# 44-pin_QFN_TQFP.net
KiCad netlist of a schematic drawn in EAGLE
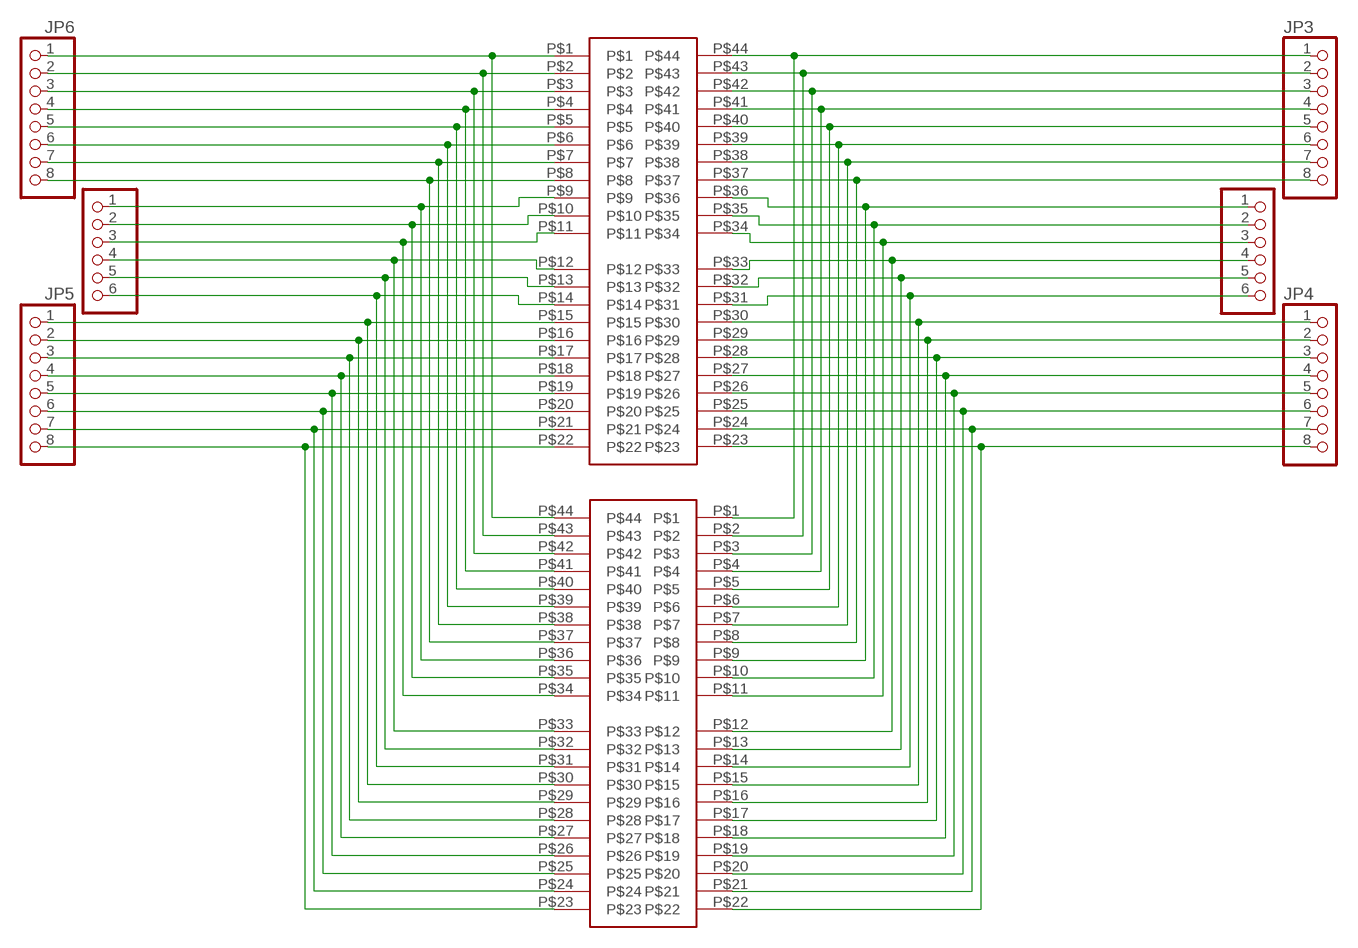
[diagram p0: schematic, sheet 1]

(export (version "E")
  (design (tool "Eeschema 10.0.6"))
  (components
    (comp (ref "JP1")
      (value "PADS-6")
      (footprint "eagle-import:PADS-6")
      (libsource (lib "eagle-import") (part "PADS-6"))
    )
    (comp (ref "JP2")
      (value "PADS-6")
      (footprint "eagle-import:PADS-6")
      (libsource (lib "eagle-import") (part "PADS-6"))
    )
    (comp (ref "JP3")
      (value "PADS-8CLEANBIG")
      (footprint "eagle-import:PADS-8")
      (libsource (lib "eagle-import") (part "PADS-8CLEANBIG"))
    )
    (comp (ref "JP4")
      (value "PADS-8CLEANBIG")
      (footprint "eagle-import:PADS-8")
      (libsource (lib "eagle-import") (part "PADS-8CLEANBIG"))
    )
    (comp (ref "JP5")
      (value "PADS-8CLEANBIG")
      (footprint "eagle-import:PADS-8")
      (libsource (lib "eagle-import") (part "PADS-8CLEANBIG"))
    )
    (comp (ref "JP6")
      (value "PADS-8CLEANBIG")
      (footprint "eagle-import:PADS-8")
      (libsource (lib "eagle-import") (part "PADS-8CLEANBIG"))
    )
    (comp (ref "U$1")
      (value "44-PINQFN")
      (footprint "eagle-import:QFN44")
      (libsource (lib "eagle-import") (part "44-PINQFN"))
    )
    (comp (ref "U$2")
      (value "44-PINTQFP")
      (footprint "eagle-import:TQFP44")
      (libsource (lib "eagle-import") (part "44-PINTQFP"))
    )
  )
  (nets
    (net (code "1") (name "Net-(JP1-Pad1)") (class "Default")
      (node (ref "JP1") (pin "1") (pinfunction "1_1") (pintype "passive"))
      (node (ref "U$1") (pin "P$36") (pinfunction "P$36_P$36") (pintype "bidirectional"))
      (node (ref "U$2") (pin "P$9") (pinfunction "P$9_P$9") (pintype "bidirectional"))
    )
    (net (code "2") (name "Net-(JP1-Pad2)") (class "Default")
      (node (ref "JP1") (pin "2") (pinfunction "2_2") (pintype "passive"))
      (node (ref "U$1") (pin "P$35") (pinfunction "P$35_P$35") (pintype "bidirectional"))
      (node (ref "U$2") (pin "P$10") (pinfunction "P$10_P$10") (pintype "bidirectional"))
    )
    (net (code "3") (name "Net-(JP1-Pad3)") (class "Default")
      (node (ref "JP1") (pin "3") (pinfunction "3_3") (pintype "passive"))
      (node (ref "U$1") (pin "P$34") (pinfunction "P$34_P$34") (pintype "bidirectional"))
      (node (ref "U$2") (pin "P$11") (pinfunction "P$11_P$11") (pintype "bidirectional"))
    )
    (net (code "4") (name "Net-(JP1-Pad4)") (class "Default")
      (node (ref "JP1") (pin "4") (pinfunction "4_4") (pintype "passive"))
      (node (ref "U$1") (pin "P$33") (pinfunction "P$33_P$33") (pintype "bidirectional"))
      (node (ref "U$2") (pin "P$12") (pinfunction "P$12_P$12") (pintype "bidirectional"))
    )
    (net (code "5") (name "Net-(JP1-Pad5)") (class "Default")
      (node (ref "JP1") (pin "5") (pinfunction "5_5") (pintype "passive"))
      (node (ref "U$1") (pin "P$32") (pinfunction "P$32_P$32") (pintype "bidirectional"))
      (node (ref "U$2") (pin "P$13") (pinfunction "P$13_P$13") (pintype "bidirectional"))
    )
    (net (code "6") (name "Net-(JP1-Pad6)") (class "Default")
      (node (ref "JP1") (pin "6") (pinfunction "6_6") (pintype "passive"))
      (node (ref "U$1") (pin "P$31") (pinfunction "P$31_P$31") (pintype "bidirectional"))
      (node (ref "U$2") (pin "P$14") (pinfunction "P$14_P$14") (pintype "bidirectional"))
    )
    (net (code "7") (name "Net-(JP2-Pad1)") (class "Default")
      (node (ref "JP2") (pin "1") (pinfunction "1_1") (pintype "passive"))
      (node (ref "U$1") (pin "P$9") (pinfunction "P$9_P$9") (pintype "bidirectional"))
      (node (ref "U$2") (pin "P$36") (pinfunction "P$36_P$36") (pintype "bidirectional"))
    )
    (net (code "8") (name "Net-(JP2-Pad2)") (class "Default")
      (node (ref "JP2") (pin "2") (pinfunction "2_2") (pintype "passive"))
      (node (ref "U$1") (pin "P$10") (pinfunction "P$10_P$10") (pintype "bidirectional"))
      (node (ref "U$2") (pin "P$35") (pinfunction "P$35_P$35") (pintype "bidirectional"))
    )
    (net (code "9") (name "Net-(JP2-Pad3)") (class "Default")
      (node (ref "JP2") (pin "3") (pinfunction "3_3") (pintype "passive"))
      (node (ref "U$1") (pin "P$11") (pinfunction "P$11_P$11") (pintype "bidirectional"))
      (node (ref "U$2") (pin "P$34") (pinfunction "P$34_P$34") (pintype "bidirectional"))
    )
    (net (code "10") (name "Net-(JP2-Pad4)") (class "Default")
      (node (ref "JP2") (pin "4") (pinfunction "4_4") (pintype "passive"))
      (node (ref "U$1") (pin "P$12") (pinfunction "P$12_P$12") (pintype "bidirectional"))
      (node (ref "U$2") (pin "P$33") (pinfunction "P$33_P$33") (pintype "bidirectional"))
    )
    (net (code "11") (name "Net-(JP2-Pad5)") (class "Default")
      (node (ref "JP2") (pin "5") (pinfunction "5_5") (pintype "passive"))
      (node (ref "U$1") (pin "P$13") (pinfunction "P$13_P$13") (pintype "bidirectional"))
      (node (ref "U$2") (pin "P$32") (pinfunction "P$32_P$32") (pintype "bidirectional"))
    )
    (net (code "12") (name "Net-(JP2-Pad6)") (class "Default")
      (node (ref "JP2") (pin "6") (pinfunction "6_6") (pintype "passive"))
      (node (ref "U$1") (pin "P$14") (pinfunction "P$14_P$14") (pintype "bidirectional"))
      (node (ref "U$2") (pin "P$31") (pinfunction "P$31_P$31") (pintype "bidirectional"))
    )
    (net (code "13") (name "Net-(JP3-Pad1)") (class "Default")
      (node (ref "JP3") (pin "1") (pinfunction "1_1") (pintype "passive"))
      (node (ref "U$1") (pin "P$44") (pinfunction "P$44_P$44") (pintype "bidirectional"))
      (node (ref "U$2") (pin "P$1") (pinfunction "P$1_P$1") (pintype "bidirectional"))
    )
    (net (code "14") (name "Net-(JP3-Pad2)") (class "Default")
      (node (ref "JP3") (pin "2") (pinfunction "2_2") (pintype "passive"))
      (node (ref "U$1") (pin "P$43") (pinfunction "P$43_P$43") (pintype "bidirectional"))
      (node (ref "U$2") (pin "P$2") (pinfunction "P$2_P$2") (pintype "bidirectional"))
    )
    (net (code "15") (name "Net-(JP3-Pad3)") (class "Default")
      (node (ref "JP3") (pin "3") (pinfunction "3_3") (pintype "passive"))
      (node (ref "U$1") (pin "P$42") (pinfunction "P$42_P$42") (pintype "bidirectional"))
      (node (ref "U$2") (pin "P$3") (pinfunction "P$3_P$3") (pintype "bidirectional"))
    )
    (net (code "16") (name "Net-(JP3-Pad4)") (class "Default")
      (node (ref "JP3") (pin "4") (pinfunction "4_4") (pintype "passive"))
      (node (ref "U$1") (pin "P$41") (pinfunction "P$41_P$41") (pintype "bidirectional"))
      (node (ref "U$2") (pin "P$4") (pinfunction "P$4_P$4") (pintype "bidirectional"))
    )
    (net (code "17") (name "Net-(JP3-Pad5)") (class "Default")
      (node (ref "JP3") (pin "5") (pinfunction "5_5") (pintype "passive"))
      (node (ref "U$1") (pin "P$40") (pinfunction "P$40_P$40") (pintype "bidirectional"))
      (node (ref "U$2") (pin "P$5") (pinfunction "P$5_P$5") (pintype "bidirectional"))
    )
    (net (code "18") (name "Net-(JP3-Pad6)") (class "Default")
      (node (ref "JP3") (pin "6") (pinfunction "6_6") (pintype "passive"))
      (node (ref "U$1") (pin "P$39") (pinfunction "P$39_P$39") (pintype "bidirectional"))
      (node (ref "U$2") (pin "P$6") (pinfunction "P$6_P$6") (pintype "bidirectional"))
    )
    (net (code "19") (name "Net-(JP3-Pad7)") (class "Default")
      (node (ref "JP3") (pin "7") (pinfunction "7_7") (pintype "passive"))
      (node (ref "U$1") (pin "P$38") (pinfunction "P$38_P$38") (pintype "bidirectional"))
      (node (ref "U$2") (pin "P$7") (pinfunction "P$7_P$7") (pintype "bidirectional"))
    )
    (net (code "20") (name "Net-(JP3-Pad8)") (class "Default")
      (node (ref "JP3") (pin "8") (pinfunction "8_8") (pintype "passive"))
      (node (ref "U$1") (pin "P$37") (pinfunction "P$37_P$37") (pintype "bidirectional"))
      (node (ref "U$2") (pin "P$8") (pinfunction "P$8_P$8") (pintype "bidirectional"))
    )
    (net (code "21") (name "Net-(JP4-Pad1)") (class "Default")
      (node (ref "JP4") (pin "1") (pinfunction "1_1") (pintype "passive"))
      (node (ref "U$1") (pin "P$30") (pinfunction "P$30_P$30") (pintype "bidirectional"))
      (node (ref "U$2") (pin "P$15") (pinfunction "P$15_P$15") (pintype "bidirectional"))
    )
    (net (code "22") (name "Net-(JP4-Pad2)") (class "Default")
      (node (ref "JP4") (pin "2") (pinfunction "2_2") (pintype "passive"))
      (node (ref "U$1") (pin "P$29") (pinfunction "P$29_P$29") (pintype "bidirectional"))
      (node (ref "U$2") (pin "P$16") (pinfunction "P$16_P$16") (pintype "bidirectional"))
    )
    (net (code "23") (name "Net-(JP4-Pad3)") (class "Default")
      (node (ref "JP4") (pin "3") (pinfunction "3_3") (pintype "passive"))
      (node (ref "U$1") (pin "P$28") (pinfunction "P$28_P$28") (pintype "bidirectional"))
      (node (ref "U$2") (pin "P$17") (pinfunction "P$17_P$17") (pintype "bidirectional"))
    )
    (net (code "24") (name "Net-(JP4-Pad4)") (class "Default")
      (node (ref "JP4") (pin "4") (pinfunction "4_4") (pintype "passive"))
      (node (ref "U$1") (pin "P$27") (pinfunction "P$27_P$27") (pintype "bidirectional"))
      (node (ref "U$2") (pin "P$18") (pinfunction "P$18_P$18") (pintype "bidirectional"))
    )
    (net (code "25") (name "Net-(JP4-Pad5)") (class "Default")
      (node (ref "JP4") (pin "5") (pinfunction "5_5") (pintype "passive"))
      (node (ref "U$1") (pin "P$26") (pinfunction "P$26_P$26") (pintype "bidirectional"))
      (node (ref "U$2") (pin "P$19") (pinfunction "P$19_P$19") (pintype "bidirectional"))
    )
    (net (code "26") (name "Net-(JP4-Pad6)") (class "Default")
      (node (ref "JP4") (pin "6") (pinfunction "6_6") (pintype "passive"))
      (node (ref "U$1") (pin "P$25") (pinfunction "P$25_P$25") (pintype "bidirectional"))
      (node (ref "U$2") (pin "P$20") (pinfunction "P$20_P$20") (pintype "bidirectional"))
    )
    (net (code "27") (name "Net-(JP4-Pad7)") (class "Default")
      (node (ref "JP4") (pin "7") (pinfunction "7_7") (pintype "passive"))
      (node (ref "U$1") (pin "P$24") (pinfunction "P$24_P$24") (pintype "bidirectional"))
      (node (ref "U$2") (pin "P$21") (pinfunction "P$21_P$21") (pintype "bidirectional"))
    )
    (net (code "28") (name "Net-(JP4-Pad8)") (class "Default")
      (node (ref "JP4") (pin "8") (pinfunction "8_8") (pintype "passive"))
      (node (ref "U$1") (pin "P$23") (pinfunction "P$23_P$23") (pintype "bidirectional"))
      (node (ref "U$2") (pin "P$22") (pinfunction "P$22_P$22") (pintype "bidirectional"))
    )
    (net (code "29") (name "Net-(JP5-Pad1)") (class "Default")
      (node (ref "JP5") (pin "1") (pinfunction "1_1") (pintype "passive"))
      (node (ref "U$1") (pin "P$15") (pinfunction "P$15_P$15") (pintype "bidirectional"))
      (node (ref "U$2") (pin "P$30") (pinfunction "P$30_P$30") (pintype "bidirectional"))
    )
    (net (code "30") (name "Net-(JP5-Pad2)") (class "Default")
      (node (ref "JP5") (pin "2") (pinfunction "2_2") (pintype "passive"))
      (node (ref "U$1") (pin "P$16") (pinfunction "P$16_P$16") (pintype "bidirectional"))
      (node (ref "U$2") (pin "P$29") (pinfunction "P$29_P$29") (pintype "bidirectional"))
    )
    (net (code "31") (name "Net-(JP5-Pad3)") (class "Default")
      (node (ref "JP5") (pin "3") (pinfunction "3_3") (pintype "passive"))
      (node (ref "U$1") (pin "P$17") (pinfunction "P$17_P$17") (pintype "bidirectional"))
      (node (ref "U$2") (pin "P$28") (pinfunction "P$28_P$28") (pintype "bidirectional"))
    )
    (net (code "32") (name "Net-(JP5-Pad4)") (class "Default")
      (node (ref "JP5") (pin "4") (pinfunction "4_4") (pintype "passive"))
      (node (ref "U$1") (pin "P$18") (pinfunction "P$18_P$18") (pintype "bidirectional"))
      (node (ref "U$2") (pin "P$27") (pinfunction "P$27_P$27") (pintype "bidirectional"))
    )
    (net (code "33") (name "Net-(JP5-Pad5)") (class "Default")
      (node (ref "JP5") (pin "5") (pinfunction "5_5") (pintype "passive"))
      (node (ref "U$1") (pin "P$19") (pinfunction "P$19_P$19") (pintype "bidirectional"))
      (node (ref "U$2") (pin "P$26") (pinfunction "P$26_P$26") (pintype "bidirectional"))
    )
    (net (code "34") (name "Net-(JP5-Pad6)") (class "Default")
      (node (ref "JP5") (pin "6") (pinfunction "6_6") (pintype "passive"))
      (node (ref "U$1") (pin "P$20") (pinfunction "P$20_P$20") (pintype "bidirectional"))
      (node (ref "U$2") (pin "P$25") (pinfunction "P$25_P$25") (pintype "bidirectional"))
    )
    (net (code "35") (name "Net-(JP5-Pad7)") (class "Default")
      (node (ref "JP5") (pin "7") (pinfunction "7_7") (pintype "passive"))
      (node (ref "U$1") (pin "P$21") (pinfunction "P$21_P$21") (pintype "bidirectional"))
      (node (ref "U$2") (pin "P$24") (pinfunction "P$24_P$24") (pintype "bidirectional"))
    )
    (net (code "36") (name "Net-(JP5-Pad8)") (class "Default")
      (node (ref "JP5") (pin "8") (pinfunction "8_8") (pintype "passive"))
      (node (ref "U$1") (pin "P$22") (pinfunction "P$22_P$22") (pintype "bidirectional"))
      (node (ref "U$2") (pin "P$23") (pinfunction "P$23_P$23") (pintype "bidirectional"))
    )
    (net (code "37") (name "Net-(JP6-Pad1)") (class "Default")
      (node (ref "JP6") (pin "1") (pinfunction "1_1") (pintype "passive"))
      (node (ref "U$1") (pin "P$1") (pinfunction "P$1_P$1") (pintype "bidirectional"))
      (node (ref "U$2") (pin "P$44") (pinfunction "P$44_P$44") (pintype "bidirectional"))
    )
    (net (code "38") (name "Net-(JP6-Pad2)") (class "Default")
      (node (ref "JP6") (pin "2") (pinfunction "2_2") (pintype "passive"))
      (node (ref "U$1") (pin "P$2") (pinfunction "P$2_P$2") (pintype "bidirectional"))
      (node (ref "U$2") (pin "P$43") (pinfunction "P$43_P$43") (pintype "bidirectional"))
    )
    (net (code "39") (name "Net-(JP6-Pad3)") (class "Default")
      (node (ref "JP6") (pin "3") (pinfunction "3_3") (pintype "passive"))
      (node (ref "U$1") (pin "P$3") (pinfunction "P$3_P$3") (pintype "bidirectional"))
      (node (ref "U$2") (pin "P$42") (pinfunction "P$42_P$42") (pintype "bidirectional"))
    )
    (net (code "40") (name "Net-(JP6-Pad4)") (class "Default")
      (node (ref "JP6") (pin "4") (pinfunction "4_4") (pintype "passive"))
      (node (ref "U$1") (pin "P$4") (pinfunction "P$4_P$4") (pintype "bidirectional"))
      (node (ref "U$2") (pin "P$41") (pinfunction "P$41_P$41") (pintype "bidirectional"))
    )
    (net (code "41") (name "Net-(JP6-Pad5)") (class "Default")
      (node (ref "JP6") (pin "5") (pinfunction "5_5") (pintype "passive"))
      (node (ref "U$1") (pin "P$5") (pinfunction "P$5_P$5") (pintype "bidirectional"))
      (node (ref "U$2") (pin "P$40") (pinfunction "P$40_P$40") (pintype "bidirectional"))
    )
    (net (code "42") (name "Net-(JP6-Pad6)") (class "Default")
      (node (ref "JP6") (pin "6") (pinfunction "6_6") (pintype "passive"))
      (node (ref "U$1") (pin "P$6") (pinfunction "P$6_P$6") (pintype "bidirectional"))
      (node (ref "U$2") (pin "P$39") (pinfunction "P$39_P$39") (pintype "bidirectional"))
    )
    (net (code "43") (name "Net-(JP6-Pad7)") (class "Default")
      (node (ref "JP6") (pin "7") (pinfunction "7_7") (pintype "passive"))
      (node (ref "U$1") (pin "P$7") (pinfunction "P$7_P$7") (pintype "bidirectional"))
      (node (ref "U$2") (pin "P$38") (pinfunction "P$38_P$38") (pintype "bidirectional"))
    )
    (net (code "44") (name "Net-(JP6-Pad8)") (class "Default")
      (node (ref "JP6") (pin "8") (pinfunction "8_8") (pintype "passive"))
      (node (ref "U$1") (pin "P$8") (pinfunction "P$8_P$8") (pintype "bidirectional"))
      (node (ref "U$2") (pin "P$37") (pinfunction "P$37_P$37") (pintype "bidirectional"))
    )
  )
)
